# 3_3V_POWER.net
KiCad netlist of a schematic drawn in Altium Designer
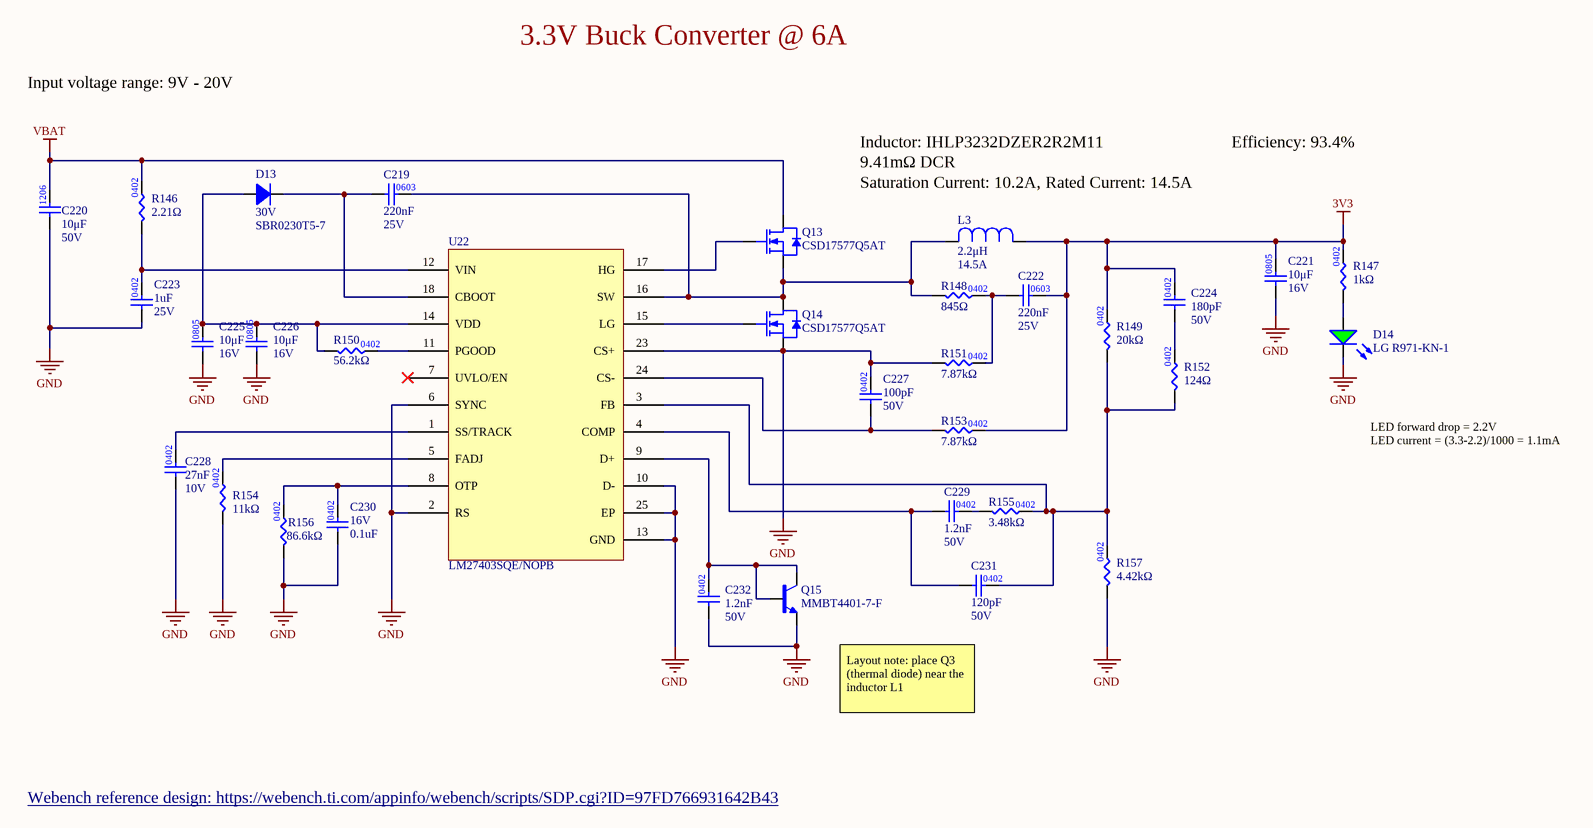
[diagram p0: 3.3V POWER.SchDoc]

(export (version "E")
  (design (tool "Eeschema 10.0.6"))
  (components
    (comp (ref "C219")
      (value "CAP_0.22uF_25V_X5R_0402")
      (footprint "CAP0402")
      (description "0.22 µF ±10% 25V Ceramic Capacitor X5R 0402 (1005 Metric)")
      (fields
        (field (name "MANUFACTURER") "Yageo")
        (field (name "MANUFACTURER PART NUMBER") "CC0402KRX5R8BB224")
        (field (name "CAPACITANCE") "220nF")
        (field (name "RATED DC VOLTAGE (URDC)") "25V")
      )
      (libsource (lib "UWRT_Schematic_Library_2020") (part "CAP_0.22uF_25V_X5R_0402"))
    )
    (comp (ref "C220")
      (value "10μF")
      (footprint "CAP1210")
      (description "CAP CER 10UF 50V X7R 1210")
      (fields (field (name "VOLTAGE RATING") "50V") (field (name "Comment") "CAP_10uF_50V_1210"))
      (libsource (lib "UWRT_Schematic_Library_2020") (part "CAP_10uF_50V_1210"))
    )
    (comp (ref "C221")
      (value "10μF")
      (footprint "CAP2012")
      (description "CAP CER 10UF 16V X5R 0805")
      (fields (field (name "VOLTAGE RATING") "16V") (field (name "Comment") "CAP_10uF_16V_0805"))
      (libsource (lib "UWRT_Schematic_Library_2020") (part "CAP_10uF_16V_0805"))
    )
    (comp (ref "C222")
      (value "CAP_0.22uF_25V_X5R_0402")
      (footprint "CAP0402")
      (description "0.22 µF ±10% 25V Ceramic Capacitor X5R 0402 (1005 Metric)")
      (fields
        (field (name "MANUFACTURER") "Yageo")
        (field (name "MANUFACTURER PART NUMBER") "CC0402KRX5R8BB224")
        (field (name "CAPACITANCE") "220nF")
        (field (name "RATED DC VOLTAGE (URDC)") "25V")
      )
      (libsource (lib "UWRT_Schematic_Library_2020") (part "CAP_0.22uF_25V_X5R_0402"))
    )
    (comp (ref "C223")
      (value "CAP_1uF_25V_0402")
      (footprint "CAP0402")
      (description "±10% 25V Ceramic Capacitor X5R 0402 (1005 Metric)")
      (fields (field (name "CAPACITANCE") "1uF") (field (name "VOLTAGE") "25V"))
      (libsource (lib "UWRT_Schematic_Library_2020") (part "CAP_1uF_25V_0402"))
    )
    (comp (ref "C224")
      (value "CAP_180pF_50V_0402")
      (footprint "CAP0402")
      (description "180 pF ±10% 50V Ceramic Capacitor X7R 0402 (1005 Metric)")
      (fields (field (name "CAPACITANCE") "180pF") (field (name "VOLTAGE") "50V"))
      (libsource (lib "UWRT_Schematic_Library_2020") (part "CAP_180pF_50V_0402"))
    )
    (comp (ref "C225")
      (value "10μF")
      (footprint "CAP2012")
      (description "CAP CER 10UF 16V X5R 0805")
      (fields (field (name "VOLTAGE RATING") "16V") (field (name "Comment") "CAP_10uF_16V_0805"))
      (libsource (lib "UWRT_Schematic_Library_2020") (part "CAP_10uF_16V_0805"))
    )
    (comp (ref "C226")
      (value "10μF")
      (footprint "CAP2012")
      (description "CAP CER 10UF 16V X5R 0805")
      (fields (field (name "VOLTAGE RATING") "16V") (field (name "Comment") "CAP_10uF_16V_0805"))
      (libsource (lib "UWRT_Schematic_Library_2020") (part "CAP_10uF_16V_0805"))
    )
    (comp (ref "C227")
      (value "CAP_100pF_50V_0402")
      (footprint "CAP0402")
      (description "100 pF ±10% 50V Ceramic Capacitor X7R 0402 (1005 Metric)")
      (fields (field (name "CAPACITANCE") "100pF") (field (name "VOLTAGE") "50V"))
      (libsource (lib "UWRT_Schematic_Library_2020") (part "CAP_100pF_50V_0402"))
    )
    (comp (ref "C228")
      (value "CAP_0.027uF_10V_X7R_0402")
      (footprint "CAP0402")
      (description "0.027 µF ±10% 10V Ceramic Capacitor X7R 0402 (1005 Metric)")
      (fields
        (field (name "MANUFACTURER") "Yageo")
        (field (name "MANUFACTURER PART NUMBER") "CC0402KRX7R6BB273")
        (field (name "CAPACITANCE") "27nF")
        (field (name "RATED DC VOLTAGE (URDC)") "10V")
      )
      (libsource (lib "UWRT_Schematic_Library_2020") (part "CAP_0.027uF_10V_X7R_0402"))
    )
    (comp (ref "C229")
      (value "CAP_1.2nF_50V_X7R_0402")
      (footprint "CAP0402")
      (description "1200 pF ±5% 50V Ceramic Capacitor X7R 0402 (1005 Metric)")
      (fields
        (field (name "MANUFACTURER") "Yageo")
        (field (name "MANUFACTURER PART NUMBER") "CC0402JRX7R9BB122")
        (field (name "CAPACITANCE") "1.2nF")
        (field (name "RATED DC VOLTAGE (URDC)") "50V")
      )
      (libsource (lib "UWRT_Schematic_Library_2020") (part "CAP_1.2nF_50V_X7R_0402"))
    )
    (comp (ref "C230")
      (value "CAP_0.1uF_16V_X7R_0402")
      (footprint "CAP0402")
      (description "Ceramic Capacitor, Ceramic")
      (fields
        (field (name "MANUFACTURER") "Taiyo Yuden")
        (field (name "MANUFACTURER PART NUMBER") "LMK212AC6106MD-T")
        (field (name "RATED DC VOLTAGE (URDC)") "16V")
        (field (name "CAPACITANCE") "0.1uF")
      )
      (libsource (lib "UWRT_Schematic_Library_2020") (part "CAP_0.1uF_16V_X7R_0402"))
    )
    (comp (ref "C231")
      (value "CAP_120pF_50V_0402")
      (footprint "CAP0402")
      (description "120 pF ±10% 50V Ceramic Capacitor X7R 0402 (1005 Metric)")
      (fields (field (name "CAPACITANCE") "120pF") (field (name "VOLTAGE") "50V"))
      (libsource (lib "UWRT_Schematic_Library_2020") (part "CAP_120pF_50V_0402"))
    )
    (comp (ref "C232")
      (value "CAP_1.2nF_50V_X7R_0402")
      (footprint "CAP0402")
      (description "1200 pF ±5% 50V Ceramic Capacitor X7R 0402 (1005 Metric)")
      (fields
        (field (name "MANUFACTURER") "Yageo")
        (field (name "MANUFACTURER PART NUMBER") "CC0402JRX7R9BB122")
        (field (name "CAPACITANCE") "1.2nF")
        (field (name "RATED DC VOLTAGE (URDC)") "50V")
      )
      (libsource (lib "UWRT_Schematic_Library_2020") (part "CAP_1.2nF_50V_X7R_0402"))
    )
    (comp (ref "D13")
      (value "30V")
      (footprint "SOD523")
      (description "Diode Super Barrier 30 V 200mA Surface Mount SOD-523")
      (fields
        (field (name "MANUFACTURER PART NUMBER 1") "SBR0230T5-7")
        (field (name "Comment") "SBR0230T5-7")
      )
      (libsource (lib "UWRT_Schematic_Library_2020") (part "DIO_30V_200mA"))
    )
    (comp (ref "D14")
      (value "DIO_LED_G")
      (footprint "LED_0805_GREEN")
      (description "LED GREEN DIFFUSED 0805 SMD")
      (fields (field (name "MANUFACTURER PART NUMBER 1") "LG R971-KN-1"))
      (libsource (lib "UWRT_Schematic_Library_2020") (part "DIO_LED_G"))
    )
    (comp (ref "L3")
      (value "IND_2.2uH_14.5A")
      (footprint "IND_VISHAY_IHLP3232DZER2R2M11")
      (description "FIXED IND 2.2UH 14.5A 9.41 MOHM")
      (fields (field (name "CURRENT RATING") "14.5A") (field (name "INDUCTANCE") "2.2μH"))
      (libsource (lib "UWRT_Schematic_Library_2020") (part "IND_2.2uH_14.5A"))
    )
    (comp (ref "Q13")
      (value "NMOS_30V_60A")
      (footprint "MOSFET_CSD19531Q5A")
      (description "MOSFET N-CH 30V 60A 8VSON")
      (fields (field (name "MANUFACTURER PART NUMBER 1") "CSD17577Q5AT"))
      (libsource (lib "UWRT_Schematic_Library_2020") (part "NMOS_30V_60A"))
    )
    (comp (ref "Q14")
      (value "NMOS_30V_60A")
      (footprint "MOSFET_CSD19531Q5A")
      (description "MOSFET N-CH 30V 60A 8VSON")
      (fields (field (name "MANUFACTURER PART NUMBER 1") "CSD17577Q5AT"))
      (libsource (lib "UWRT_Schematic_Library_2020") (part "NMOS_30V_60A"))
    )
    (comp (ref "Q15")
      (value "MMBT4401-7-F")
      (footprint "MMBT4401-7-F")
      (description "Bipolar (BJT) Transistor NPN 40 V 600 mA 250MHz 310 mW Surface Mount SOT-23-3")
      (libsource (lib "UWRT_Schematic_Library_2020") (part "MMBT4401-7-F"))
    )
    (comp (ref "R146")
      (value "2.21Ω")
      (footprint "RES0402")
      (description "RES 2.21 OHM 1% 1/16W 0402")
      (fields (field (name "POWER") "0.063W, 1/16W") (field (name "TOLERANCE") "1%"))
      (libsource (lib "UWRT_Schematic_Library_2020") (part "RES_2.21Ω_0402_1%"))
    )
    (comp (ref "R147")
      (value "RES_1kΩ_0402")
      (footprint "RES0402")
      (fields
        (field (name "MANUFACTURER") "Stackpole Electronics")
        (field (name "MANUFACTURER PART NUMBER") "RMCF0402FT1K00")
        (field (name "TOLERANCE") "1%")
        (field (name "RESISTANCE") "1kΩ")
      )
      (libsource (lib "UWRT_Schematic_Library_2020") (part "RES_1kΩ_0402"))
    )
    (comp (ref "R148")
      (value "845Ω")
      (footprint "RES0402")
      (description "RES SMD 845 OHM 1% 1/16W 0402")
      (fields (field (name "POWER") "0.063W, 1/16W") (field (name "TOLERANCE") "1%"))
      (libsource (lib "UWRT_Schematic_Library_2020") (part "RES_845Ω_0402_1%"))
    )
    (comp (ref "R149")
      (value "20kΩ")
      (footprint "RES0402")
      (description "RES SMD 20K OHM 1% 1/16W 0402")
      (fields (field (name "POWER") "0.063W, 1/16W") (field (name "TOLERANCE") "1%"))
      (libsource (lib "UWRT_Schematic_Library_2020") (part "RES_20kΩ_0402_1%"))
    )
    (comp (ref "R150")
      (value "56.2kΩ")
      (footprint "RES0402")
      (description "RES SMD 56.2K OHM 1% 1/16W 0402")
      (fields (field (name "POWER") "0.063W, 1/16W") (field (name "TOLERANCE") "1%"))
      (libsource (lib "UWRT_Schematic_Library_2020") (part "RES_56.2kΩ_0402_1%"))
    )
    (comp (ref "R151")
      (value "7.87kΩ")
      (footprint "RES0402")
      (description "RES 7.87K OHM 1% 1/16W 0402")
      (fields (field (name "POWER") "0.063W, 1/16W") (field (name "TOLERANCE") "1%"))
      (libsource (lib "UWRT_Schematic_Library_2020") (part "RES_7.87kΩ_0402_1%"))
    )
    (comp (ref "R152")
      (value "124Ω")
      (footprint "RES0402")
      (description "RES SMD 124 OHM 1% 1/16W 0402")
      (fields (field (name "POWER") "0.063W, 1/16W") (field (name "TOLERANCE") "1%"))
      (libsource (lib "UWRT_Schematic_Library_2020") (part "RES_124Ω_0402_1%"))
    )
    (comp (ref "R153")
      (value "7.87kΩ")
      (footprint "RES0402")
      (description "RES 7.87K OHM 1% 1/16W 0402")
      (fields (field (name "POWER") "0.063W, 1/16W") (field (name "TOLERANCE") "1%"))
      (libsource (lib "UWRT_Schematic_Library_2020") (part "RES_7.87kΩ_0402_1%"))
    )
    (comp (ref "R154")
      (value "11kΩ")
      (footprint "RES0402")
      (description "RES 11K OHM 1% 1/16W 0402")
      (fields (field (name "POWER") "0.063W, 1/16W") (field (name "TOLERANCE") "1%"))
      (libsource (lib "UWRT_Schematic_Library_2020") (part "RES_11kΩ_0402_1%"))
    )
    (comp (ref "R155")
      (value "3.48kΩ")
      (footprint "RES0402")
      (description "RES SMD 3.48K OHM 1% 1/16W 0402")
      (fields (field (name "POWER") "0.063W, 1/16W") (field (name "TOLERANCE") "1%"))
      (libsource (lib "UWRT_Schematic_Library_2020") (part "RES_3.48kΩ_0402_1%"))
    )
    (comp (ref "R156")
      (value "86.6kΩ")
      (footprint "RES0402")
      (description "RES SMD 86.6K OHM 1% 1/16W 0402")
      (fields (field (name "POWER") "0.063W, 1/16W") (field (name "TOLERANCE") "1%"))
      (libsource (lib "UWRT_Schematic_Library_2020") (part "RES_86.6kΩ_0402_1%"))
    )
    (comp (ref "R157")
      (value "4.42kΩ")
      (footprint "RES0402")
      (description "RES 4.42K OHM 1% 1/16W 0402")
      (fields (field (name "POWER") "0.063W, 1/16W") (field (name "TOLERANCE") "1%"))
      (libsource (lib "UWRT_Schematic_Library_2020") (part "RES_4.42kΩ_0402_1%"))
    )
    (comp (ref "U22")
      (value "LM27403SQE/NOPB")
      (footprint "QFN50P400X400X80-25N")
      (description "Buck Regulator Positive Output Step-Down - DC-DC Controller IC 24-WQFN (4x4)")
      (libsource (lib "UWRT_Schematic_Library_2020") (part "LM27403SQE/NOPB"))
    )
  )
  (nets
    (net (code "1") (name "3V3") (class "Default")
      (node (ref "C221") (pin "2") (pinfunction "2_2") (pintype "passive"))
      (node (ref "C222") (pin "2") (pinfunction "2_2") (pintype "passive"))
      (node (ref "C224") (pin "2") (pinfunction "2_2") (pintype "passive"))
      (node (ref "L3") (pin "1") (pinfunction "1_1") (pintype "passive"))
      (node (ref "R147") (pin "2") (pinfunction "2_2") (pintype "passive"))
      (node (ref "R149") (pin "2") (pinfunction "2_2") (pintype "passive"))
      (node (ref "R153") (pin "2") (pinfunction "2_2") (pintype "passive"))
    )
    (net (code "2") (name "GND") (class "Default")
      (node (ref "C220") (pin "1") (pinfunction "1_1") (pintype "passive"))
      (node (ref "C221") (pin "1") (pinfunction "1_1") (pintype "passive"))
      (node (ref "C223") (pin "1") (pinfunction "1_1") (pintype "passive"))
      (node (ref "C225") (pin "1") (pinfunction "1_1") (pintype "passive"))
      (node (ref "C226") (pin "1") (pinfunction "1_1") (pintype "passive"))
      (node (ref "C227") (pin "2") (pinfunction "2_2") (pintype "passive"))
      (node (ref "C228") (pin "1") (pinfunction "1_1") (pintype "passive"))
      (node (ref "C230") (pin "1") (pinfunction "1_1") (pintype "passive"))
      (node (ref "C232") (pin "1") (pinfunction "1_1") (pintype "passive"))
      (node (ref "D14") (pin "2") (pinfunction "K_2") (pintype "passive"))
      (node (ref "Q14") (pin "1") (pinfunction "Source_1") (pintype "passive"))
      (node (ref "Q15") (pin "2") (pinfunction "2_2") (pintype "passive"))
      (node (ref "R151") (pin "1") (pinfunction "1_1") (pintype "passive"))
      (node (ref "R154") (pin "1") (pinfunction "1_1") (pintype "passive"))
      (node (ref "R156") (pin "1") (pinfunction "1_1") (pintype "passive"))
      (node (ref "R157") (pin "1") (pinfunction "1_1") (pintype "passive"))
      (node (ref "U22") (pin "10") (pinfunction "D-_10") (pintype "passive"))
      (node (ref "U22") (pin "13") (pinfunction "GND_13") (pintype "passive"))
      (node (ref "U22") (pin "2") (pinfunction "RS_2") (pintype "passive"))
      (node (ref "U22") (pin "23") (pinfunction "CS+_23") (pintype "passive"))
      (node (ref "U22") (pin "25") (pinfunction "EP_25") (pintype "passive"))
      (node (ref "U22") (pin "6") (pinfunction "SYNC_6") (pintype "passive"))
    )
    (net (code "3") (name "Net-(C222-Pad1)") (class "Default")
      (node (ref "C222") (pin "1") (pinfunction "1_1") (pintype "passive"))
      (node (ref "R148") (pin "2") (pinfunction "2_2") (pintype "passive"))
      (node (ref "R151") (pin "2") (pinfunction "2_2") (pintype "passive"))
    )
    (net (code "4") (name "Net-(C224-Pad1)") (class "Default")
      (node (ref "C224") (pin "1") (pinfunction "1_1") (pintype "passive"))
      (node (ref "R152") (pin "2") (pinfunction "2_2") (pintype "passive"))
    )
    (net (code "5") (name "Net-(C229-Pad2)") (class "Default")
      (node (ref "C229") (pin "2") (pinfunction "2_2") (pintype "passive"))
      (node (ref "R155") (pin "1") (pinfunction "1_1") (pintype "passive"))
    )
    (net (code "6") (name "Net-(D14-A)") (class "Default")
      (node (ref "D14") (pin "1") (pinfunction "A_1") (pintype "passive"))
      (node (ref "R147") (pin "1") (pinfunction "1_1") (pintype "passive"))
    )
    (net (code "7") (name "Net-(Q13-Gate)") (class "Default")
      (node (ref "Q13") (pin "2") (pinfunction "Gate_2") (pintype "passive"))
      (node (ref "U22") (pin "17") (pinfunction "HG_17") (pintype "passive"))
    )
    (net (code "8") (name "Net-(Q13-Source)") (class "Default")
      (node (ref "C219") (pin "2") (pinfunction "2_2") (pintype "passive"))
      (node (ref "L3") (pin "2") (pinfunction "2_2") (pintype "passive"))
      (node (ref "Q13") (pin "1") (pinfunction "Source_1") (pintype "passive"))
      (node (ref "Q14") (pin "3") (pinfunction "Drain_3") (pintype "passive"))
      (node (ref "R148") (pin "1") (pinfunction "1_1") (pintype "passive"))
      (node (ref "U22") (pin "16") (pinfunction "SW_16") (pintype "passive"))
    )
    (net (code "9") (name "Net-(Q14-Gate)") (class "Default")
      (node (ref "Q14") (pin "2") (pinfunction "Gate_2") (pintype "passive"))
      (node (ref "U22") (pin "15") (pinfunction "LG_15") (pintype "passive"))
    )
    (net (code "10") (name "Net-(U22-CBOOT)") (class "Default")
      (node (ref "C219") (pin "1") (pinfunction "1_1") (pintype "passive"))
      (node (ref "D13") (pin "1") (pintype "passive"))
      (node (ref "U22") (pin "18") (pinfunction "CBOOT_18") (pintype "passive"))
    )
    (net (code "11") (name "Net-(U22-COMP)") (class "Default")
      (node (ref "C229") (pin "1") (pinfunction "1_1") (pintype "passive"))
      (node (ref "C231") (pin "1") (pinfunction "1_1") (pintype "passive"))
      (node (ref "U22") (pin "4") (pinfunction "COMP_4") (pintype "passive"))
    )
    (net (code "12") (name "Net-(U22-CS-)") (class "Default")
      (node (ref "C227") (pin "1") (pinfunction "1_1") (pintype "passive"))
      (node (ref "R153") (pin "1") (pinfunction "1_1") (pintype "passive"))
      (node (ref "U22") (pin "24") (pinfunction "CS-_24") (pintype "passive"))
    )
    (net (code "13") (name "Net-(U22-D+)") (class "Default")
      (node (ref "C232") (pin "2") (pinfunction "2_2") (pintype "passive"))
      (node (ref "Q15") (pin "1") (pinfunction "1_1") (pintype "passive"))
      (node (ref "Q15") (pin "3") (pinfunction "3_3") (pintype "passive"))
      (node (ref "U22") (pin "9") (pinfunction "D+_9") (pintype "passive"))
    )
    (net (code "14") (name "Net-(U22-FADJ)") (class "Default")
      (node (ref "R154") (pin "2") (pinfunction "2_2") (pintype "passive"))
      (node (ref "U22") (pin "5") (pinfunction "FADJ_5") (pintype "passive"))
    )
    (net (code "15") (name "Net-(U22-FB)") (class "Default")
      (node (ref "C231") (pin "2") (pinfunction "2_2") (pintype "passive"))
      (node (ref "R149") (pin "1") (pinfunction "1_1") (pintype "passive"))
      (node (ref "R152") (pin "1") (pinfunction "1_1") (pintype "passive"))
      (node (ref "R155") (pin "2") (pinfunction "2_2") (pintype "passive"))
      (node (ref "R157") (pin "2") (pinfunction "2_2") (pintype "passive"))
      (node (ref "U22") (pin "3") (pinfunction "FB_3") (pintype "passive"))
    )
    (net (code "16") (name "Net-(U22-OTP)") (class "Default")
      (node (ref "C230") (pin "2") (pinfunction "2_2") (pintype "passive"))
      (node (ref "R156") (pin "2") (pinfunction "2_2") (pintype "passive"))
      (node (ref "U22") (pin "8") (pinfunction "OTP_8") (pintype "passive"))
    )
    (net (code "17") (name "Net-(U22-PGOOD)") (class "Default")
      (node (ref "R150") (pin "2") (pinfunction "2_2") (pintype "passive"))
      (node (ref "U22") (pin "11") (pinfunction "PGOOD_11") (pintype "passive"))
    )
    (net (code "18") (name "Net-(U22-SS{slash}TRACK)") (class "Default")
      (node (ref "C228") (pin "2") (pinfunction "2_2") (pintype "passive"))
      (node (ref "U22") (pin "1") (pinfunction "SS/TRACK_1") (pintype "passive"))
    )
    (net (code "19") (name "Net-(U22-VDD)") (class "Default")
      (node (ref "C225") (pin "2") (pinfunction "2_2") (pintype "passive"))
      (node (ref "C226") (pin "2") (pinfunction "2_2") (pintype "passive"))
      (node (ref "D13") (pin "2") (pintype "passive"))
      (node (ref "R150") (pin "1") (pinfunction "1_1") (pintype "passive"))
      (node (ref "U22") (pin "14") (pinfunction "VDD_14") (pintype "passive"))
    )
    (net (code "20") (name "Net-(U22-VIN)") (class "Default")
      (node (ref "C223") (pin "2") (pinfunction "2_2") (pintype "passive"))
      (node (ref "R146") (pin "1") (pinfunction "1_1") (pintype "passive"))
      (node (ref "U22") (pin "12") (pinfunction "VIN_12") (pintype "passive"))
    )
    (net (code "21") (name "VBAT") (class "Default")
      (node (ref "C220") (pin "2") (pinfunction "2_2") (pintype "passive"))
      (node (ref "Q13") (pin "3") (pinfunction "Drain_3") (pintype "passive"))
      (node (ref "R146") (pin "2") (pinfunction "2_2") (pintype "passive"))
    )
    (net (code "22") (name "unconnected-(U22-UVLO{slash}EN-Pad7)") (class "Default")
      (node (ref "U22") (pin "7") (pinfunction "UVLO/EN_7") (pintype "passive+no_connect"))
    )
  )
)
